# CON_CF.net
KiCad netlist of a schematic drawn in Altium Designer
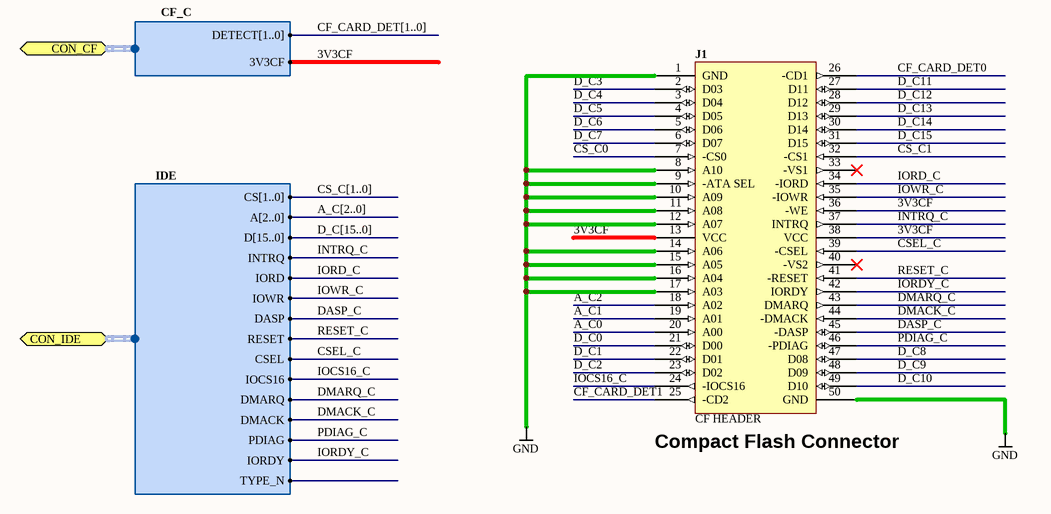
[diagram p0: CON_CF.SchDoc]

(export (version "E")
  (design (tool "Eeschema 10.0.6"))
  (components
    (comp (ref "J1")
      (value "CF HEADER")
      (footprint "CF_SM0_635-6H50B")
      (description "Connector, Compact Flash Card Adaptor Top-side")
      (libsource (lib "AltiumDesignLibrary") (part "CON-CF"))
    )
  )
  (nets
    (net (code "3") (name "/3V3CF") (class "Default")
      (node (ref "J1") (pin "13") (pinfunction "VCC_13") (pintype "power_in"))
      (node (ref "J1") (pin "36") (pinfunction "-WE_36") (pintype "input"))
      (node (ref "J1") (pin "38") (pinfunction "VCC_38") (pintype "power_in"))
    )
    (net (code "4") (name "/A_C0") (class "Default")
      (node (ref "J1") (pin "20") (pinfunction "A00_20") (pintype "input"))
    )
    (net (code "5") (name "/A_C1") (class "Default")
      (node (ref "J1") (pin "19") (pinfunction "A01_19") (pintype "input"))
    )
    (net (code "6") (name "/A_C2") (class "Default")
      (node (ref "J1") (pin "18") (pinfunction "A02_18") (pintype "input"))
    )
    (net (code "8") (name "/CF_CARD_DET0") (class "Default")
      (node (ref "J1") (pin "26") (pinfunction "-CD1_26") (pintype "output"))
    )
    (net (code "9") (name "/CF_CARD_DET1") (class "Default")
      (node (ref "J1") (pin "25") (pinfunction "-CD2_25") (pintype "output"))
    )
    (net (code "12") (name "/CSEL_C") (class "Default")
      (node (ref "J1") (pin "39") (pinfunction "-CSEL_39") (pintype "input"))
    )
    (net (code "13") (name "/CS_C0") (class "Default")
      (node (ref "J1") (pin "7") (pinfunction "-CS0_7") (pintype "input"))
    )
    (net (code "14") (name "/CS_C1") (class "Default")
      (node (ref "J1") (pin "32") (pinfunction "-CS1_32") (pintype "input"))
    )
    (net (code "16") (name "/DASP_C") (class "Default")
      (node (ref "J1") (pin "45") (pinfunction "-DASP_45") (pintype "bidirectional"))
    )
    (net (code "17") (name "/DMACK_C") (class "Default")
      (node (ref "J1") (pin "44") (pinfunction "-DMACK_44") (pintype "input"))
    )
    (net (code "18") (name "/DMARQ_C") (class "Default")
      (node (ref "J1") (pin "43") (pinfunction "DMARQ_43") (pintype "output"))
    )
    (net (code "19") (name "/D_C0") (class "Default")
      (node (ref "J1") (pin "21") (pinfunction "D00_21") (pintype "bidirectional"))
    )
    (net (code "20") (name "/D_C1") (class "Default")
      (node (ref "J1") (pin "22") (pinfunction "D01_22") (pintype "bidirectional"))
    )
    (net (code "21") (name "/D_C2") (class "Default")
      (node (ref "J1") (pin "23") (pinfunction "D02_23") (pintype "bidirectional"))
    )
    (net (code "22") (name "/D_C3") (class "Default")
      (node (ref "J1") (pin "2") (pinfunction "D03_2") (pintype "bidirectional"))
    )
    (net (code "23") (name "/D_C4") (class "Default")
      (node (ref "J1") (pin "3") (pinfunction "D04_3") (pintype "bidirectional"))
    )
    (net (code "24") (name "/D_C5") (class "Default")
      (node (ref "J1") (pin "4") (pinfunction "D05_4") (pintype "bidirectional"))
    )
    (net (code "25") (name "/D_C6") (class "Default")
      (node (ref "J1") (pin "5") (pinfunction "D06_5") (pintype "bidirectional"))
    )
    (net (code "26") (name "/D_C7") (class "Default")
      (node (ref "J1") (pin "6") (pinfunction "D07_6") (pintype "bidirectional"))
    )
    (net (code "27") (name "/D_C8") (class "Default")
      (node (ref "J1") (pin "47") (pinfunction "D08_47") (pintype "bidirectional"))
    )
    (net (code "28") (name "/D_C9") (class "Default")
      (node (ref "J1") (pin "48") (pinfunction "D09_48") (pintype "bidirectional"))
    )
    (net (code "29") (name "/D_C10") (class "Default")
      (node (ref "J1") (pin "49") (pinfunction "D10_49") (pintype "bidirectional"))
    )
    (net (code "30") (name "/D_C11") (class "Default")
      (node (ref "J1") (pin "27") (pinfunction "D11_27") (pintype "bidirectional"))
    )
    (net (code "31") (name "/D_C12") (class "Default")
      (node (ref "J1") (pin "28") (pinfunction "D12_28") (pintype "bidirectional"))
    )
    (net (code "32") (name "/D_C13") (class "Default")
      (node (ref "J1") (pin "29") (pinfunction "D13_29") (pintype "bidirectional"))
    )
    (net (code "33") (name "/D_C14") (class "Default")
      (node (ref "J1") (pin "30") (pinfunction "D14_30") (pintype "bidirectional"))
    )
    (net (code "34") (name "/D_C15") (class "Default")
      (node (ref "J1") (pin "31") (pinfunction "D15_31") (pintype "bidirectional"))
    )
    (net (code "35") (name "/INTRQ_C") (class "Default")
      (node (ref "J1") (pin "37") (pinfunction "INTRQ_37") (pintype "output"))
    )
    (net (code "36") (name "/IOCS16_C") (class "Default")
      (node (ref "J1") (pin "24") (pinfunction "-IOCS16_24") (pintype "output"))
    )
    (net (code "37") (name "/IORDY_C") (class "Default")
      (node (ref "J1") (pin "42") (pinfunction "IORDY_42") (pintype "output"))
    )
    (net (code "38") (name "/IORD_C") (class "Default")
      (node (ref "J1") (pin "34") (pinfunction "-IORD_34") (pintype "input"))
    )
    (net (code "39") (name "/IOWR_C") (class "Default")
      (node (ref "J1") (pin "35") (pinfunction "-IOWR_35") (pintype "input"))
    )
    (net (code "40") (name "/PDIAG_C") (class "Default")
      (node (ref "J1") (pin "46") (pinfunction "-PDIAG_46") (pintype "bidirectional"))
    )
    (net (code "41") (name "/RESET_C") (class "Default")
      (node (ref "J1") (pin "41") (pinfunction "-RESET_41") (pintype "input"))
    )
    (net (code "44") (name "GND") (class "Default")
      (node (ref "J1") (pin "1") (pinfunction "GND_1") (pintype "power_in"))
      (node (ref "J1") (pin "10") (pinfunction "A09_10") (pintype "input"))
      (node (ref "J1") (pin "11") (pinfunction "A08_11") (pintype "input"))
      (node (ref "J1") (pin "12") (pinfunction "A07_12") (pintype "input"))
      (node (ref "J1") (pin "14") (pinfunction "A06_14") (pintype "input"))
      (node (ref "J1") (pin "15") (pinfunction "A05_15") (pintype "input"))
      (node (ref "J1") (pin "16") (pinfunction "A04_16") (pintype "input"))
      (node (ref "J1") (pin "17") (pinfunction "A03_17") (pintype "input"))
      (node (ref "J1") (pin "50") (pinfunction "GND_50") (pintype "power_in"))
      (node (ref "J1") (pin "8") (pinfunction "A10_8") (pintype "input"))
      (node (ref "J1") (pin "9") (pinfunction "-ATA_SEL_9") (pintype "input"))
    )
    (net (code "45") (name "unconnected-(J1--VS1-Pad33)") (class "Default")
      (node (ref "J1") (pin "33") (pinfunction "-VS1_33") (pintype "output+no_connect"))
    )
    (net (code "46") (name "unconnected-(J1--VS2-Pad40)") (class "Default")
      (node (ref "J1") (pin "40") (pinfunction "-VS2_40") (pintype "output+no_connect"))
    )
  )
)
